# xcomm.net
KiCad netlist of a schematic drawn in Altium Designer
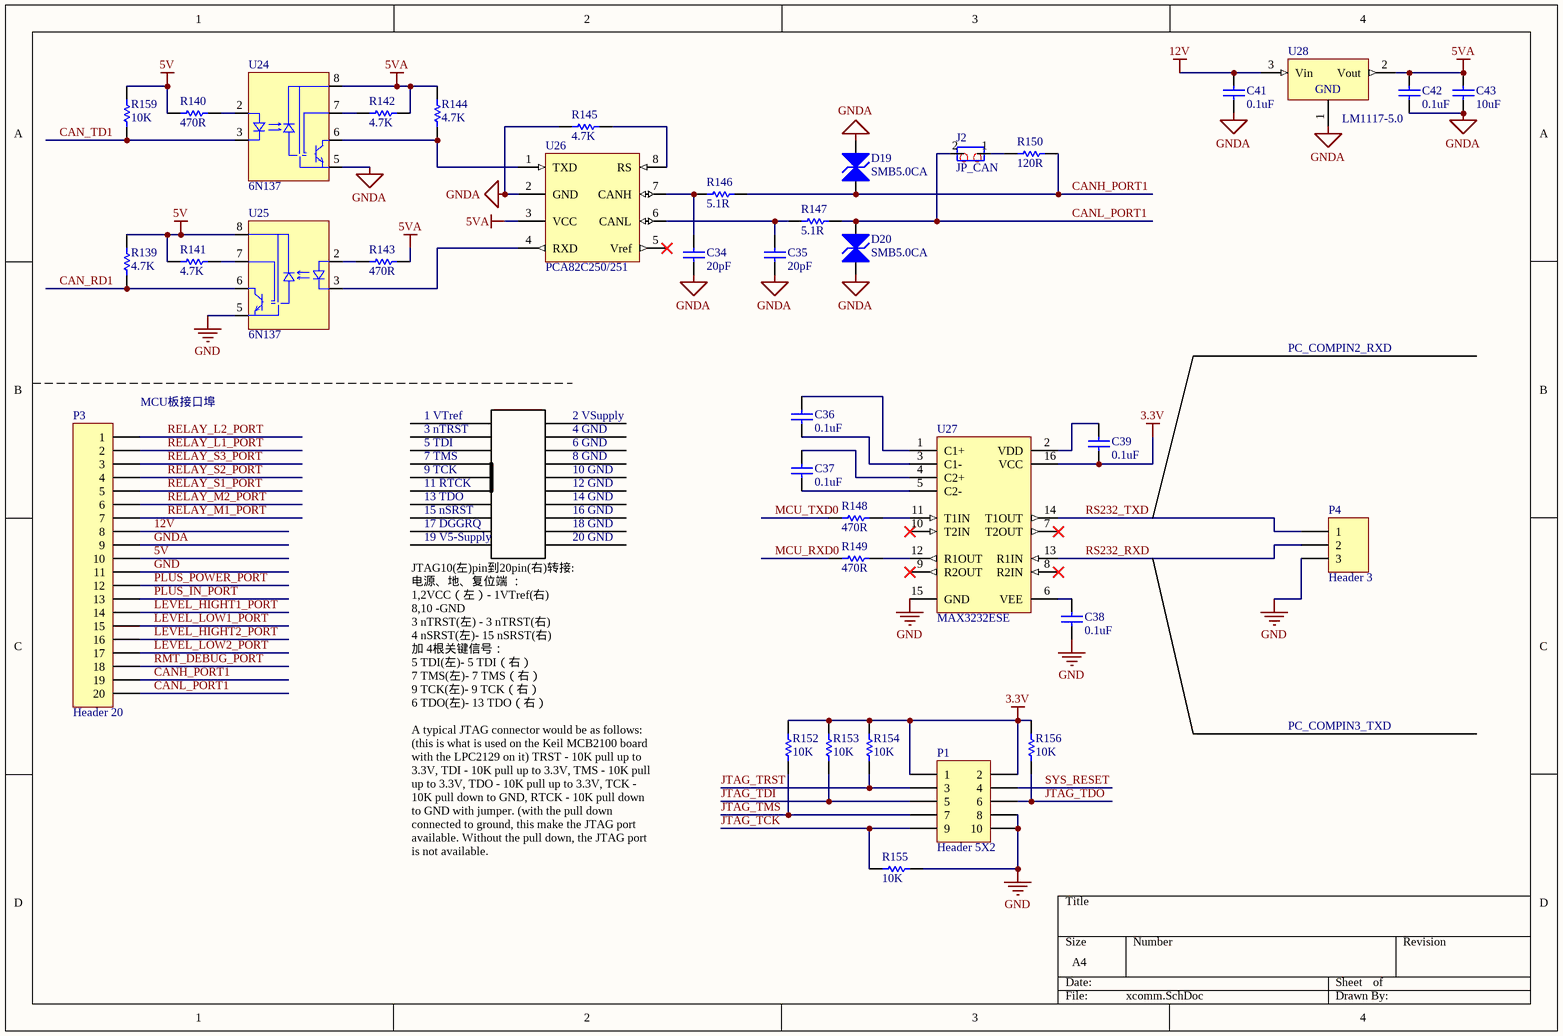
[diagram p0: xcomm.SchDoc]

(export (version "E")
  (design (tool "Eeschema 10.0.6"))
  (components
    (comp (ref "C34")
      (value "20pF")
      (footprint "CAPC2012M")
      (description "Capacitor")
      (fields (field (name "PUBLISHER") "Altium Limited"))
      (libsource (lib "Miscellaneous Devices") (part "Cap"))
    )
    (comp (ref "C35")
      (value "20pF")
      (footprint "CAPC2012M")
      (description "Capacitor")
      (fields (field (name "PUBLISHER") "Altium Limited"))
      (libsource (lib "Miscellaneous Devices") (part "Cap"))
    )
    (comp (ref "C36")
      (value "0.1uF")
      (footprint "CAPC2012M")
      (description "Capacitor")
      (fields (field (name "PUBLISHER") "Altium Limited"))
      (libsource (lib "Miscellaneous Devices") (part "Cap"))
    )
    (comp (ref "C37")
      (value "0.1uF")
      (footprint "CAPC2012M")
      (description "Capacitor")
      (fields (field (name "PUBLISHER") "Altium Limited"))
      (libsource (lib "Miscellaneous Devices") (part "Cap"))
    )
    (comp (ref "C38")
      (value "0.1uF")
      (footprint "CAPC2012M")
      (description "Capacitor")
      (fields (field (name "PUBLISHER") "Altium Limited"))
      (libsource (lib "Miscellaneous Devices") (part "Cap"))
    )
    (comp (ref "C39")
      (value "0.1uF")
      (footprint "CAPC2012M")
      (description "Capacitor")
      (fields (field (name "PUBLISHER") "Altium Limited"))
      (libsource (lib "Miscellaneous Devices") (part "Cap"))
    )
    (comp (ref "C41")
      (value "0.1uF")
      (footprint "CAPC2012M")
      (description "Capacitor")
      (fields (field (name "PUBLISHER") "Altium Limited"))
      (libsource (lib "Miscellaneous Devices") (part "Cap"))
    )
    (comp (ref "C42")
      (value "0.1uF")
      (footprint "CAPC2012M")
      (description "Capacitor")
      (fields (field (name "PUBLISHER") "Altium Limited"))
      (libsource (lib "Miscellaneous Devices") (part "Cap"))
    )
    (comp (ref "C43")
      (value "10uF")
      (footprint "CAPC2012M")
      (description "Capacitor")
      (fields (field (name "PUBLISHER") "Altium Limited"))
      (libsource (lib "Miscellaneous Devices") (part "Cap"))
    )
    (comp (ref "D19")
      (value "SMB5.0CA")
      (footprint "SMB")
      (description "Bi-dir TVS Diode")
      (fields (field (name "PUBLISHER") "Altium Limited"))
      (libsource (lib "UserLib") (part "Bi-dir TVS Diode"))
    )
    (comp (ref "D20")
      (value "SMB5.0CA")
      (footprint "SMB")
      (description "Bi-dir TVS Diode")
      (fields (field (name "PUBLISHER") "Altium Limited"))
      (libsource (lib "UserLib") (part "Bi-dir TVS Diode"))
    )
    (comp (ref "J2")
      (value "JP_CAN")
      (footprint "DS-01")
      (description "'Dial Switch pitch 7.62mm")
      (libsource (lib "UserLib") (part "JK2H"))
    )
    (comp (ref "P1")
      (value "Header 5X2")
      (footprint "HDR2X5M")
      (description "Header, 5-Pin, Dual row,Pitch 2mm")
      (fields (field (name "PUBLISHER") "Altium Limited"))
      (libsource (lib "Miscellaneous Connectors") (part "Header 5X2"))
    )
    (comp (ref "P3")
      (value "Header 20")
      (footprint "HDR1X20-2.5")
      (description "'Wafer Header, 20-Pin,white")
      (fields (field (name "PUBLISHER") "Altium Limited"))
      (libsource (lib "Miscellaneous Connectors") (part "Header 20"))
    )
    (comp (ref "P4")
      (value "Header 3")
      (footprint "HDR1X3-2.5")
      (description "'Wafer Header, 3-Pin,white")
      (fields (field (name "PUBLISHER") "Altium Limited"))
      (libsource (lib "Miscellaneous Connectors") (part "Header 3"))
    )
    (comp (ref "R139")
      (value "4.7K")
      (footprint "RESC2012M")
      (description "Resistor")
      (fields (field (name "PUBLISHER") "Altium Limited"))
      (libsource (lib "Miscellaneous Devices") (part "Res1"))
    )
    (comp (ref "R140")
      (value "470R")
      (footprint "RESC2012M")
      (description "Resistor")
      (fields (field (name "PUBLISHER") "Altium Limited"))
      (libsource (lib "Miscellaneous Devices") (part "Res1"))
    )
    (comp (ref "R141")
      (value "4.7K")
      (footprint "RESC2012M")
      (description "Resistor")
      (fields (field (name "PUBLISHER") "Altium Limited"))
      (libsource (lib "Miscellaneous Devices") (part "Res1"))
    )
    (comp (ref "R142")
      (value "4.7K")
      (footprint "RESC2012M")
      (description "Resistor")
      (fields (field (name "PUBLISHER") "Altium Limited"))
      (libsource (lib "Miscellaneous Devices") (part "Res1"))
    )
    (comp (ref "R143")
      (value "470R")
      (footprint "RESC2012M")
      (description "Resistor")
      (fields (field (name "PUBLISHER") "Altium Limited"))
      (libsource (lib "Miscellaneous Devices") (part "Res1"))
    )
    (comp (ref "R144")
      (value "4.7K")
      (footprint "RESC2012M")
      (description "Resistor")
      (fields (field (name "PUBLISHER") "Altium Limited"))
      (libsource (lib "Miscellaneous Devices") (part "Res1"))
    )
    (comp (ref "R145")
      (value "4.7K")
      (footprint "RESC2012M")
      (description "Resistor")
      (fields (field (name "PUBLISHER") "Altium Limited"))
      (libsource (lib "Miscellaneous Devices") (part "Res1"))
    )
    (comp (ref "R146")
      (value "5.1R")
      (footprint "RESC2012M")
      (description "Resistor")
      (fields (field (name "PUBLISHER") "Altium Limited"))
      (libsource (lib "Miscellaneous Devices") (part "Res1"))
    )
    (comp (ref "R147")
      (value "5.1R")
      (footprint "RESC2012M")
      (description "Resistor")
      (fields (field (name "PUBLISHER") "Altium Limited"))
      (libsource (lib "Miscellaneous Devices") (part "Res1"))
    )
    (comp (ref "R148")
      (value "470R")
      (footprint "RESC2012M")
      (description "Resistor")
      (fields (field (name "PUBLISHER") "Altium Limited"))
      (libsource (lib "Miscellaneous Devices") (part "Res1"))
    )
    (comp (ref "R149")
      (value "470R")
      (footprint "RESC2012M")
      (description "Resistor")
      (fields (field (name "PUBLISHER") "Altium Limited"))
      (libsource (lib "Miscellaneous Devices") (part "Res1"))
    )
    (comp (ref "R150")
      (value "120R")
      (footprint "RESC2012M")
      (description "Resistor")
      (fields (field (name "PUBLISHER") "Altium Limited"))
      (libsource (lib "Miscellaneous Devices") (part "Res1"))
    )
    (comp (ref "R152")
      (value "10K")
      (footprint "RESC2012M")
      (description "Resistor")
      (fields (field (name "PUBLISHER") "Altium Limited"))
      (libsource (lib "Miscellaneous Devices") (part "Res1"))
    )
    (comp (ref "R153")
      (value "10K")
      (footprint "RESC2012M")
      (description "Resistor")
      (fields (field (name "PUBLISHER") "Altium Limited"))
      (libsource (lib "Miscellaneous Devices") (part "Res1"))
    )
    (comp (ref "R154")
      (value "10K")
      (footprint "RESC2012M")
      (description "Resistor")
      (fields (field (name "PUBLISHER") "Altium Limited"))
      (libsource (lib "Miscellaneous Devices") (part "Res1"))
    )
    (comp (ref "R155")
      (value "10K")
      (footprint "RESC2012M")
      (description "Resistor")
      (fields (field (name "PUBLISHER") "Altium Limited"))
      (libsource (lib "Miscellaneous Devices") (part "Res1"))
    )
    (comp (ref "R156")
      (value "10K")
      (footprint "RESC2012M")
      (description "Resistor")
      (fields (field (name "PUBLISHER") "Altium Limited"))
      (libsource (lib "Miscellaneous Devices") (part "Res1"))
    )
    (comp (ref "R159")
      (value "10K")
      (footprint "RESC2012M")
      (description "Resistor")
      (fields (field (name "PUBLISHER") "Altium Limited"))
      (libsource (lib "Miscellaneous Devices") (part "Res1"))
    )
    (comp (ref "U24")
      (value "6N137")
      (footprint "SO-8LA")
      (description "Hight Speed 10Mbit/s Logic Gate Optocoupler")
      (libsource (lib "") (part "HCPL-2601/2611_1"))
    )
    (comp (ref "U25")
      (value "6N137")
      (footprint "SO-8LA")
      (description "Hight Speed 10Mbit/s Logic Gate Optocoupler")
      (libsource (lib "UserLib") (part "HCPL-2601/2611"))
    )
    (comp (ref "U26")
      (value "PCA82C250/251")
      (footprint "SO8")
      (description "CAN controller bus transceiver")
      (libsource (lib "UserLib") (part "PCA82C250/251"))
    )
    (comp (ref "U27")
      (value "MAX3232ESE")
      (footprint "NSO16_N")
      (description "+5V Powered, Multi-Channel RS-232 Driver/Receiver")
      (fields (field (name "PUBLISHER") "Altium Limited"))
      (libsource (lib "Maxim Communication Transceiver") (part "MAX232ESE"))
    )
    (comp (ref "U28")
      (value "LM1117-5.0")
      (footprint "SOT-223")
      (description "800mA Low-Dropout Linear Regulator")
      (libsource (lib "UserLib") (part "LM1117T-5.0"))
    )
  )
  (nets
    (net (code "1") (name "/CANH_PORT1") (class "Default")
      (node (ref "D19") (pin "2") (pinfunction "K_2") (pintype "passive"))
      (node (ref "P3") (pin "19") (pinfunction "19_19") (pintype "passive"))
      (node (ref "R146") (pin "1") (pinfunction "1_1") (pintype "passive"))
      (node (ref "R150") (pin "2") (pinfunction "2_2") (pintype "passive"))
    )
    (net (code "2") (name "/CANL_PORT1") (class "Default")
      (node (ref "D20") (pin "2") (pinfunction "K_2") (pintype "passive"))
      (node (ref "J2") (pin "2") (pintype "passive"))
      (node (ref "P3") (pin "20") (pinfunction "20_20") (pintype "passive"))
      (node (ref "R147") (pin "1") (pinfunction "1_1") (pintype "passive"))
    )
    (net (code "3") (name "/CAN_RD1") (class "Default")
      (node (ref "R139") (pin "2") (pinfunction "2_2") (pintype "passive"))
      (node (ref "U25") (pin "6") (pinfunction "Vo_6") (pintype "passive"))
    )
    (net (code "4") (name "/CAN_TD1") (class "Default")
      (node (ref "R159") (pin "2") (pinfunction "2_2") (pintype "passive"))
      (node (ref "U24") (pin "3") (pinfunction "K_3") (pintype "passive"))
    )
    (net (code "5") (name "/JTAG_TCK") (class "Default")
      (node (ref "P1") (pin "9") (pinfunction "9_9") (pintype "passive"))
      (node (ref "R155") (pin "1") (pinfunction "1_1") (pintype "passive"))
    )
    (net (code "6") (name "/JTAG_TDI") (class "Default")
      (node (ref "P1") (pin "5") (pinfunction "5_5") (pintype "passive"))
      (node (ref "R153") (pin "1") (pinfunction "1_1") (pintype "passive"))
    )
    (net (code "7") (name "/JTAG_TDO") (class "Default")
      (node (ref "P1") (pin "6") (pinfunction "6_6") (pintype "passive"))
      (node (ref "R156") (pin "1") (pinfunction "1_1") (pintype "passive"))
    )
    (net (code "8") (name "/JTAG_TMS") (class "Default")
      (node (ref "P1") (pin "7") (pinfunction "7_7") (pintype "passive"))
      (node (ref "R152") (pin "1") (pinfunction "1_1") (pintype "passive"))
    )
    (net (code "9") (name "/JTAG_TRST") (class "Default")
      (node (ref "P1") (pin "3") (pinfunction "3_3") (pintype "passive"))
      (node (ref "R154") (pin "1") (pinfunction "1_1") (pintype "passive"))
    )
    (net (code "10") (name "/LEVEL_HIGHT1_PORT") (class "Default")
      (node (ref "P3") (pin "14") (pinfunction "14_14") (pintype "passive"))
    )
    (net (code "11") (name "/LEVEL_HIGHT2_PORT") (class "Default")
      (node (ref "P3") (pin "16") (pinfunction "16_16") (pintype "passive"))
    )
    (net (code "12") (name "/LEVEL_LOW1_PORT") (class "Default")
      (node (ref "P3") (pin "15") (pinfunction "15_15") (pintype "passive"))
    )
    (net (code "13") (name "/LEVEL_LOW2_PORT") (class "Default")
      (node (ref "P3") (pin "17") (pinfunction "17_17") (pintype "passive"))
    )
    (net (code "14") (name "/MCU_RXD0") (class "Default")
      (node (ref "R149") (pin "1") (pinfunction "1_1") (pintype "passive"))
    )
    (net (code "15") (name "/MCU_TXD0") (class "Default")
      (node (ref "R148") (pin "1") (pinfunction "1_1") (pintype "passive"))
    )
    (net (code "16") (name "/PLUS_IN_PORT") (class "Default")
      (node (ref "P3") (pin "13") (pinfunction "13_13") (pintype "passive"))
    )
    (net (code "17") (name "/PLUS_POWER_PORT") (class "Default")
      (node (ref "P3") (pin "12") (pinfunction "12_12") (pintype "passive"))
    )
    (net (code "18") (name "/RELAY_L1_PORT") (class "Default")
      (node (ref "P3") (pin "2") (pinfunction "2_2") (pintype "passive"))
    )
    (net (code "19") (name "/RELAY_L2_PORT") (class "Default")
      (node (ref "P3") (pin "1") (pinfunction "1_1") (pintype "passive"))
    )
    (net (code "20") (name "/RELAY_M1_PORT") (class "Default")
      (node (ref "P3") (pin "7") (pinfunction "7_7") (pintype "passive"))
    )
    (net (code "21") (name "/RELAY_M2_PORT") (class "Default")
      (node (ref "P3") (pin "6") (pinfunction "6_6") (pintype "passive"))
    )
    (net (code "22") (name "/RELAY_S1_PORT") (class "Default")
      (node (ref "P3") (pin "5") (pinfunction "5_5") (pintype "passive"))
    )
    (net (code "23") (name "/RELAY_S2_PORT") (class "Default")
      (node (ref "P3") (pin "4") (pinfunction "4_4") (pintype "passive"))
    )
    (net (code "24") (name "/RELAY_S3_PORT") (class "Default")
      (node (ref "P3") (pin "3") (pinfunction "3_3") (pintype "passive"))
    )
    (net (code "25") (name "/RMT_DEBUG_PORT") (class "Default")
      (node (ref "P3") (pin "18") (pinfunction "18_18") (pintype "passive"))
    )
    (net (code "26") (name "/RS232_RXD") (class "Default")
      (node (ref "P4") (pin "2") (pinfunction "2_2") (pintype "passive"))
      (node (ref "U27") (pin "13") (pinfunction "R1IN_13") (pintype "input"))
    )
    (net (code "27") (name "/RS232_TXD") (class "Default")
      (node (ref "P4") (pin "1") (pinfunction "1_1") (pintype "passive"))
      (node (ref "U27") (pin "14") (pinfunction "T1OUT_14") (pintype "output"))
    )
    (net (code "28") (name "/SYS_RESET") (class "Default")
      (node (ref "P1") (pin "4") (pinfunction "4_4") (pintype "passive"))
    )
    (net (code "29") (name "3.3V") (class "Default")
      (node (ref "C39") (pin "2") (pinfunction "2_2") (pintype "passive"))
      (node (ref "P1") (pin "1") (pinfunction "1_1") (pintype "passive"))
      (node (ref "P1") (pin "2") (pinfunction "2_2") (pintype "passive"))
      (node (ref "R152") (pin "2") (pinfunction "2_2") (pintype "passive"))
      (node (ref "R153") (pin "2") (pinfunction "2_2") (pintype "passive"))
      (node (ref "R154") (pin "2") (pinfunction "2_2") (pintype "passive"))
      (node (ref "R156") (pin "2") (pinfunction "2_2") (pintype "passive"))
      (node (ref "U27") (pin "16") (pinfunction "VCC_16") (pintype "power_in"))
    )
    (net (code "30") (name "5V") (class "Default")
      (node (ref "P3") (pin "10") (pinfunction "10_10") (pintype "passive"))
      (node (ref "R139") (pin "1") (pinfunction "1_1") (pintype "passive"))
      (node (ref "R140") (pin "2") (pinfunction "2_2") (pintype "passive"))
      (node (ref "R141") (pin "1") (pinfunction "1_1") (pintype "passive"))
      (node (ref "R159") (pin "1") (pinfunction "1_1") (pintype "passive"))
      (node (ref "U25") (pin "8") (pinfunction "VCC_8") (pintype "power_in"))
    )
    (net (code "31") (name "5VA") (class "Default")
      (node (ref "C42") (pin "2") (pinfunction "2_2") (pintype "passive"))
      (node (ref "C43") (pin "2") (pinfunction "2_2") (pintype "passive"))
      (node (ref "R142") (pin "1") (pinfunction "1_1") (pintype "passive"))
      (node (ref "R143") (pin "2") (pinfunction "2_2") (pintype "passive"))
      (node (ref "R144") (pin "1") (pinfunction "1_1") (pintype "passive"))
      (node (ref "U24") (pin "8") (pinfunction "VCC_8") (pintype "power_in"))
      (node (ref "U26") (pin "3") (pinfunction "VCC_3") (pintype "open_emitter"))
      (node (ref "U28") (pin "2") (pinfunction "Vout_2") (pintype "output"))
    )
    (net (code "32") (name "12V") (class "Default")
      (node (ref "C41") (pin "2") (pinfunction "2_2") (pintype "passive"))
      (node (ref "P3") (pin "8") (pinfunction "8_8") (pintype "passive"))
      (node (ref "U28") (pin "3") (pinfunction "Vin_3") (pintype "input"))
    )
    (net (code "33") (name "GND") (class "Default")
      (node (ref "C38") (pin "1") (pinfunction "1_1") (pintype "passive"))
      (node (ref "P1") (pin "10") (pinfunction "10_10") (pintype "passive"))
      (node (ref "P1") (pin "8") (pinfunction "8_8") (pintype "passive"))
      (node (ref "P3") (pin "11") (pinfunction "11_11") (pintype "passive"))
      (node (ref "P4") (pin "3") (pinfunction "3_3") (pintype "passive"))
      (node (ref "R155") (pin "2") (pinfunction "2_2") (pintype "passive"))
      (node (ref "U25") (pin "5") (pinfunction "GND_5") (pintype "passive"))
      (node (ref "U27") (pin "15") (pinfunction "GND_15") (pintype "power_in"))
    )
    (net (code "34") (name "GNDA") (class "Default")
      (node (ref "C34") (pin "1") (pinfunction "1_1") (pintype "passive"))
      (node (ref "C35") (pin "1") (pinfunction "1_1") (pintype "passive"))
      (node (ref "C41") (pin "1") (pinfunction "1_1") (pintype "passive"))
      (node (ref "C42") (pin "1") (pinfunction "1_1") (pintype "passive"))
      (node (ref "C43") (pin "1") (pinfunction "1_1") (pintype "passive"))
      (node (ref "D19") (pin "1") (pinfunction "A_1") (pintype "passive"))
      (node (ref "D20") (pin "1") (pinfunction "A_1") (pintype "passive"))
      (node (ref "P3") (pin "9") (pinfunction "9_9") (pintype "passive"))
      (node (ref "R145") (pin "1") (pinfunction "1_1") (pintype "passive"))
      (node (ref "U24") (pin "5") (pinfunction "GND_5") (pintype "passive"))
      (node (ref "U26") (pin "2") (pinfunction "GND_2") (pintype "power_in"))
      (node (ref "U28") (pin "1") (pinfunction "GND_1") (pintype "passive"))
    )
    (net (code "35") (name "Net-(J2-Pad1)") (class "Default")
      (node (ref "J2") (pin "1") (pintype "passive"))
      (node (ref "R150") (pin "1") (pinfunction "1_1") (pintype "passive"))
    )
    (net (code "36") (name "Net-(U24-A)") (class "Default")
      (node (ref "R140") (pin "1") (pinfunction "1_1") (pintype "passive"))
      (node (ref "U24") (pin "2") (pinfunction "A_2") (pintype "passive"))
    )
    (net (code "37") (name "Net-(U24-Ve)") (class "Default")
      (node (ref "R142") (pin "2") (pinfunction "2_2") (pintype "passive"))
      (node (ref "U24") (pin "7") (pinfunction "Ve_7") (pintype "passive"))
    )
    (net (code "38") (name "Net-(U24-Vo)") (class "Default")
      (node (ref "R144") (pin "2") (pinfunction "2_2") (pintype "passive"))
      (node (ref "U24") (pin "6") (pinfunction "Vo_6") (pintype "passive"))
      (node (ref "U26") (pin "1") (pinfunction "TXD_1") (pintype "input"))
    )
    (net (code "39") (name "Net-(U25-A)") (class "Default")
      (node (ref "R143") (pin "1") (pinfunction "1_1") (pintype "passive"))
      (node (ref "U25") (pin "2") (pinfunction "A_2") (pintype "passive"))
    )
    (net (code "40") (name "Net-(U25-K)") (class "Default")
      (node (ref "U25") (pin "3") (pinfunction "K_3") (pintype "passive"))
      (node (ref "U26") (pin "4") (pinfunction "RXD_4") (pintype "output"))
    )
    (net (code "41") (name "Net-(U25-Ve)") (class "Default")
      (node (ref "R141") (pin "2") (pinfunction "2_2") (pintype "passive"))
      (node (ref "U25") (pin "7") (pinfunction "Ve_7") (pintype "passive"))
    )
    (net (code "42") (name "Net-(U26-CANH)") (class "Default")
      (node (ref "C34") (pin "2") (pinfunction "2_2") (pintype "passive"))
      (node (ref "R146") (pin "2") (pinfunction "2_2") (pintype "passive"))
      (node (ref "U26") (pin "7") (pinfunction "CANH_7") (pintype "bidirectional"))
    )
    (net (code "43") (name "Net-(U26-CANL)") (class "Default")
      (node (ref "C35") (pin "2") (pinfunction "2_2") (pintype "passive"))
      (node (ref "R147") (pin "2") (pinfunction "2_2") (pintype "passive"))
      (node (ref "U26") (pin "6") (pinfunction "CANL_6") (pintype "bidirectional"))
    )
    (net (code "44") (name "Net-(U26-RS)") (class "Default")
      (node (ref "R145") (pin "2") (pinfunction "2_2") (pintype "passive"))
      (node (ref "U26") (pin "8") (pinfunction "RS_8") (pintype "input"))
    )
    (net (code "45") (name "Net-(U27-C1+)") (class "Default")
      (node (ref "C36") (pin "2") (pinfunction "2_2") (pintype "passive"))
      (node (ref "U27") (pin "1") (pinfunction "C1+_1") (pintype "passive"))
    )
    (net (code "46") (name "Net-(U27-C1-)") (class "Default")
      (node (ref "C36") (pin "1") (pinfunction "1_1") (pintype "passive"))
      (node (ref "U27") (pin "3") (pinfunction "C1-_3") (pintype "passive"))
    )
    (net (code "47") (name "Net-(U27-C2+)") (class "Default")
      (node (ref "C37") (pin "2") (pinfunction "2_2") (pintype "passive"))
      (node (ref "U27") (pin "4") (pinfunction "C2+_4") (pintype "passive"))
    )
    (net (code "48") (name "Net-(U27-C2-)") (class "Default")
      (node (ref "C37") (pin "1") (pinfunction "1_1") (pintype "passive"))
      (node (ref "U27") (pin "5") (pinfunction "C2-_5") (pintype "passive"))
    )
    (net (code "49") (name "Net-(U27-R1OUT)") (class "Default")
      (node (ref "R149") (pin "2") (pinfunction "2_2") (pintype "passive"))
      (node (ref "U27") (pin "12") (pinfunction "R1OUT_12") (pintype "output"))
    )
    (net (code "50") (name "Net-(U27-T1IN)") (class "Default")
      (node (ref "R148") (pin "2") (pinfunction "2_2") (pintype "passive"))
      (node (ref "U27") (pin "11") (pinfunction "T1IN_11") (pintype "input"))
    )
    (net (code "51") (name "Net-(U27-VDD)") (class "Default")
      (node (ref "C39") (pin "1") (pinfunction "1_1") (pintype "passive"))
      (node (ref "U27") (pin "2") (pinfunction "VDD_2") (pintype "power_in"))
    )
    (net (code "52") (name "Net-(U27-VEE)") (class "Default")
      (node (ref "C38") (pin "2") (pinfunction "2_2") (pintype "passive"))
      (node (ref "U27") (pin "6") (pinfunction "VEE_6") (pintype "power_in"))
    )
    (net (code "53") (name "unconnected-(U26-Vref-Pad5)") (class "Default")
      (node (ref "U26") (pin "5") (pinfunction "Vref_5") (pintype "output+no_connect"))
    )
    (net (code "54") (name "unconnected-(U27-R2IN-Pad8)") (class "Default")
      (node (ref "U27") (pin "8") (pinfunction "R2IN_8") (pintype "input+no_connect"))
    )
    (net (code "55") (name "unconnected-(U27-R2OUT-Pad9)") (class "Default")
      (node (ref "U27") (pin "9") (pinfunction "R2OUT_9") (pintype "output+no_connect"))
    )
    (net (code "56") (name "unconnected-(U27-T2IN-Pad10)") (class "Default")
      (node (ref "U27") (pin "10") (pinfunction "T2IN_10") (pintype "input+no_connect"))
    )
    (net (code "57") (name "unconnected-(U27-T2OUT-Pad7)") (class "Default")
      (node (ref "U27") (pin "7") (pinfunction "T2OUT_7") (pintype "output+no_connect"))
    )
  )
)
